# Harvester.net
KiCad netlist of a schematic drawn in Altium Designer
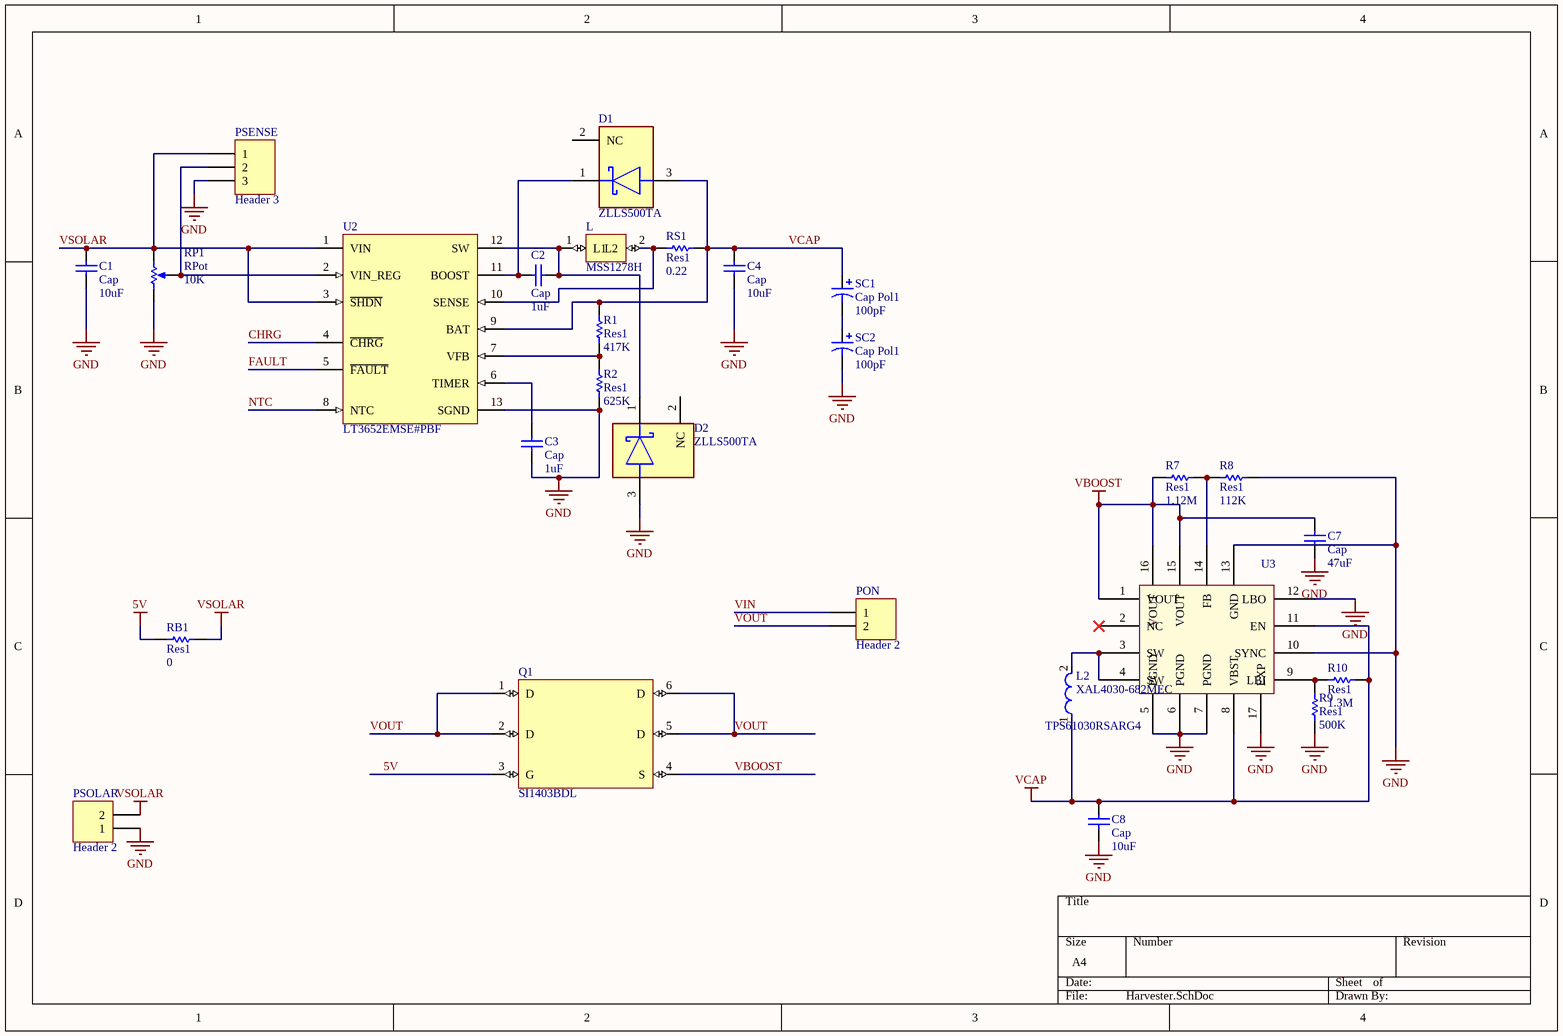
[diagram p0: Harvester.SchDoc]

(export (version "E")
  (design (tool "Eeschema 10.0.6"))
  (components
    (comp (ref "C1")
      (value "Cap")
      (footprint "1812")
      (description "Capacitor")
      (fields (field (name "ALTIUM_VALUE") "10uF") (field (name "PUBLISHER") "Altium Limited"))
      (libsource (lib "Miscellaneous Devices") (part "Cap"))
    )
    (comp (ref "C2")
      (value "Cap")
      (footprint "1812")
      (description "Capacitor")
      (fields (field (name "ALTIUM_VALUE") "1uF") (field (name "PUBLISHER") "Altium Limited"))
      (libsource (lib "Miscellaneous Devices") (part "Cap"))
    )
    (comp (ref "C3")
      (value "Cap")
      (footprint "1812")
      (description "Capacitor")
      (fields (field (name "ALTIUM_VALUE") "1uF") (field (name "PUBLISHER") "Altium Limited"))
      (libsource (lib "Miscellaneous Devices") (part "Cap"))
    )
    (comp (ref "C4")
      (value "Cap")
      (footprint "1812")
      (description "Capacitor")
      (fields (field (name "ALTIUM_VALUE") "10uF") (field (name "PUBLISHER") "Altium Limited"))
      (libsource (lib "Miscellaneous Devices") (part "Cap"))
    )
    (comp (ref "C7")
      (value "Cap")
      (footprint "1812")
      (description "Capacitor")
      (fields (field (name "ALTIUM_VALUE") "47uF") (field (name "PUBLISHER") "Altium Limited"))
      (libsource (lib "Miscellaneous Devices") (part "Cap"))
    )
    (comp (ref "C8")
      (value "Cap")
      (footprint "1608[0603]")
      (description "Capacitor")
      (fields (field (name "ALTIUM_VALUE") "10uF") (field (name "PUBLISHER") "Altium Limited"))
      (libsource (lib "Miscellaneous Devices") (part "Cap"))
    )
    (comp (ref "D1")
      (value "ZLLS500TA")
      (footprint "FP-SOT23-IPC_B")
      (description "DIODE SCHOTTKY 40V 700MA SOT23-3")
      (libsource (lib "") (part "b02bf5cfd78647b0d44792585de17e4_1"))
    )
    (comp (ref "D2")
      (value "ZLLS500TA")
      (footprint "FP-SOT23-IPC_B")
      (description "DIODE SCHOTTKY 40V 700MA SOT23-3")
      (libsource (lib "Altium Content Vault") (part "b02bf5cfd78647b0d44792585de17e4"))
    )
    (comp (ref "L") (value "MSS1278H") (footprint "MSS1278H") (libsource (lib "MSS1278H") (part "MSS1278H")))
    (comp (ref "L2")
      (value "XAL4030-682MEC")
      (footprint "FP-XAL4030-472MEC-MFG")
      (description "Power Inductor (SMD), 6.8 µH, 5.1 A, Shielded, 4.5 A, XAL40xx Series, 4mm x 4mm x 3.1mm")
      (fields (field (name "TOLERANCE") "20%"))
      (libsource (lib "Altium Content Vault") (part "725321dda6339637d4d059423bc1c3c"))
    )
    (comp (ref "PON")
      (value "Header 2")
      (footprint "HDR1X2")
      (description "Header, 2-Pin")
      (fields (field (name "PUBLISHER") "Altium Limited"))
      (libsource (lib "Miscellaneous Connectors") (part "Header 2"))
    )
    (comp (ref "PSENSE")
      (value "Header 3")
      (footprint "HDR1X3")
      (description "Header, 3-Pin")
      (fields (field (name "PUBLISHER") "Altium Limited"))
      (libsource (lib "Miscellaneous Connectors") (part "Header 3"))
    )
    (comp (ref "PSOLAR")
      (value "Header 2")
      (footprint "HDR1X2")
      (description "Header, 2-Pin")
      (fields (field (name "PUBLISHER") "Altium Limited"))
      (libsource (lib "") (part "Header 2_1"))
    )
    (comp (ref "Q1")
      (value "SI1403BDL")
      (footprint "SI1403BDL")
      (description "RC (Pi) EMI Filter 2nd Order Low Pass 2 Channel R = 33Ohms, C = 47pF 6-TSSOP, SC-88, SOT-363")
      (fields (field (name "MP") "USBUF01W6") (field (name "MF") "STMicroelectronics"))
      (libsource (lib "SI1403BDL") (part "SI1403BDL"))
    )
    (comp (ref "R1")
      (value "Res1")
      (footprint "0603R-GENERIC")
      (description "Resistor")
      (fields (field (name "ALTIUM_VALUE") "417K") (field (name "PUBLISHER") "Altium Limited"))
      (libsource (lib "Miscellaneous Devices") (part "Res1"))
    )
    (comp (ref "R2")
      (value "Res1")
      (footprint "0603R-GENERIC")
      (description "Resistor")
      (fields (field (name "ALTIUM_VALUE") "625K") (field (name "PUBLISHER") "Altium Limited"))
      (libsource (lib "Miscellaneous Devices") (part "Res1"))
    )
    (comp (ref "R7")
      (value "Res1")
      (footprint "0603R-GENERIC")
      (description "Resistor")
      (fields (field (name "ALTIUM_VALUE") "1.12M") (field (name "PUBLISHER") "Altium Limited"))
      (libsource (lib "Miscellaneous Devices") (part "Res1"))
    )
    (comp (ref "R8")
      (value "Res1")
      (footprint "0603R-GENERIC")
      (description "Resistor")
      (fields (field (name "ALTIUM_VALUE") "112K") (field (name "PUBLISHER") "Altium Limited"))
      (libsource (lib "Miscellaneous Devices") (part "Res1"))
    )
    (comp (ref "R9")
      (value "Res1")
      (footprint "0603R-GENERIC")
      (description "Resistor")
      (fields (field (name "ALTIUM_VALUE") "500K") (field (name "PUBLISHER") "Altium Limited"))
      (libsource (lib "Miscellaneous Devices") (part "Res1"))
    )
    (comp (ref "R10")
      (value "Res1")
      (footprint "0603R-GENERIC")
      (description "Resistor")
      (fields (field (name "ALTIUM_VALUE") "1.3M") (field (name "PUBLISHER") "Altium Limited"))
      (libsource (lib "Miscellaneous Devices") (part "Res1"))
    )
    (comp (ref "RB1")
      (value "Res1")
      (footprint "0603R-GENERIC")
      (description "Resistor")
      (fields (field (name "ALTIUM_VALUE") "0") (field (name "PUBLISHER") "Altium Limited"))
      (libsource (lib "Miscellaneous Devices") (part "Res1"))
    )
    (comp (ref "RP1")
      (value "RPot")
      (footprint "VR5")
      (description "Potentiometer")
      (fields (field (name "ALTIUM_VALUE") "10K") (field (name "PUBLISHER") "Altium Limited"))
      (libsource (lib "Miscellaneous Devices") (part "RPot"))
    )
    (comp (ref "RS1")
      (value "Res1")
      (footprint "0603R-GENERIC")
      (description "Resistor")
      (fields (field (name "ALTIUM_VALUE") "0.22") (field (name "PUBLISHER") "Altium Limited"))
      (libsource (lib "Miscellaneous Devices") (part "Res1"))
    )
    (comp (ref "SC1")
      (value "Cap Pol1")
      (footprint "RB7.6-15")
      (description "Polarized Capacitor (Radial)")
      (fields (field (name "ALTIUM_VALUE") "100pF") (field (name "PUBLISHER") "Altium Limited"))
      (libsource (lib "Miscellaneous Devices") (part "Cap Pol1"))
    )
    (comp (ref "SC2")
      (value "Cap Pol1")
      (footprint "RB7.6-15")
      (description "Polarized Capacitor (Radial)")
      (fields (field (name "ALTIUM_VALUE") "100pF") (field (name "PUBLISHER") "Altium Limited"))
      (libsource (lib "Miscellaneous Devices") (part "Cap Pol1"))
    )
    (comp (ref "U2")
      (value "LT3652EMSE#PBF")
      (footprint "LT-MSE-12-EDP_M")
      (fields (field (name "MANUFACTURER") "Linear Technology"))
      (libsource (lib "Altium Content Vault") (part "LT-LT3652-MSE-12_3652HV-DD-12"))
    )
    (comp (ref "U3")
      (value "TPS61030RSARG4")
      (footprint "QFN65P400X400X100-17N")
      (libsource (lib "TPS61030RSARG4") (part "TPS61030RSARG4"))
    )
  )
  (nets
    (net (code "1") (name "/CHRG") (class "Default")
      (node (ref "U2") (pin "4") (pinfunction "~{CHRG}_4") (pintype "tri_state"))
    )
    (net (code "2") (name "/FAULT") (class "Default")
      (node (ref "U2") (pin "5") (pinfunction "~{FAULT}_5") (pintype "tri_state"))
    )
    (net (code "3") (name "/NTC") (class "Default")
      (node (ref "U2") (pin "8") (pinfunction "NTC_8") (pintype "input"))
    )
    (net (code "4") (name "/VIN") (class "Default")
      (node (ref "PON") (pin "1") (pinfunction "1_1") (pintype "passive"))
    )
    (net (code "5") (name "/VOUT") (class "Default")
      (node (ref "PON") (pin "2") (pinfunction "2_2") (pintype "passive"))
      (node (ref "Q1") (pin "1") (pinfunction "D_1") (pintype "bidirectional"))
      (node (ref "Q1") (pin "2") (pinfunction "D_2") (pintype "bidirectional"))
      (node (ref "Q1") (pin "5") (pinfunction "D_5") (pintype "bidirectional"))
      (node (ref "Q1") (pin "6") (pinfunction "D_6") (pintype "bidirectional"))
    )
    (net (code "6") (name "5V") (class "Default")
      (node (ref "Q1") (pin "3") (pinfunction "G_3") (pintype "bidirectional"))
      (node (ref "RB1") (pin "1") (pinfunction "1_1") (pintype "passive"))
    )
    (net (code "7") (name "GND") (class "Default")
      (node (ref "C1") (pin "2") (pinfunction "2_2") (pintype "passive"))
      (node (ref "C3") (pin "2") (pinfunction "2_2") (pintype "passive"))
      (node (ref "C4") (pin "2") (pinfunction "2_2") (pintype "passive"))
      (node (ref "C7") (pin "1") (pinfunction "1_1") (pintype "passive"))
      (node (ref "C8") (pin "1") (pinfunction "1_1") (pintype "passive"))
      (node (ref "D2") (pin "3") (pinfunction "A_3") (pintype "passive"))
      (node (ref "PSENSE") (pin "3") (pinfunction "3_3") (pintype "passive"))
      (node (ref "PSOLAR") (pin "1") (pinfunction "1_1") (pintype "passive"))
      (node (ref "R2") (pin "2") (pinfunction "2_2") (pintype "passive"))
      (node (ref "R8") (pin "1") (pinfunction "1_1") (pintype "passive"))
      (node (ref "R9") (pin "2") (pinfunction "2_2") (pintype "passive"))
      (node (ref "RP1") (pin "1") (pinfunction "TOP_1") (pintype "passive"))
      (node (ref "SC2") (pin "2") (pinfunction "2_2") (pintype "passive"))
      (node (ref "U2") (pin "13") (pinfunction "SGND_13") (pintype "power_in"))
      (node (ref "U3") (pin "10") (pinfunction "SYNC_10") (pintype "passive"))
      (node (ref "U3") (pin "12") (pinfunction "LBO_12") (pintype "passive"))
      (node (ref "U3") (pin "13") (pinfunction "GND_13") (pintype "passive"))
      (node (ref "U3") (pin "17") (pinfunction "EXP_17") (pintype "passive"))
      (node (ref "U3") (pin "5") (pinfunction "PGND_5") (pintype "passive"))
      (node (ref "U3") (pin "6") (pinfunction "PGND_6") (pintype "passive"))
      (node (ref "U3") (pin "7") (pinfunction "PGND_7") (pintype "passive"))
    )
    (net (code "8") (name "Net-(D1-C)") (class "Default")
      (node (ref "C2") (pin "1") (pinfunction "1_1") (pintype "passive"))
      (node (ref "D1") (pin "1") (pinfunction "C_1") (pintype "passive"))
      (node (ref "U2") (pin "11") (pinfunction "BOOST_11") (pintype "power_in"))
    )
    (net (code "9") (name "Net-(D2-C)") (class "Default")
      (node (ref "C2") (pin "2") (pinfunction "2_2") (pintype "passive"))
      (node (ref "D2") (pin "1") (pinfunction "C_1") (pintype "passive"))
      (node (ref "L") (pin "1") (pinfunction "L1_1") (pintype "bidirectional"))
      (node (ref "U2") (pin "12") (pinfunction "SW_12") (pintype "power_in"))
    )
    (net (code "10") (name "Net-(L-L2)") (class "Default")
      (node (ref "L") (pin "2") (pinfunction "L2_2") (pintype "bidirectional"))
      (node (ref "RS1") (pin "1") (pinfunction "1_1") (pintype "passive"))
      (node (ref "U2") (pin "10") (pinfunction "SENSE_10") (pintype "input"))
    )
    (net (code "11") (name "Net-(L2-Pad2)") (class "Default")
      (node (ref "L2") (pin "2") (pinfunction "2_2") (pintype "passive"))
      (node (ref "U3") (pin "3") (pinfunction "SW_3") (pintype "passive"))
      (node (ref "U3") (pin "4") (pinfunction "SW_4") (pintype "passive"))
    )
    (net (code "12") (name "Net-(RP1-TAP)") (class "Default")
      (node (ref "PSENSE") (pin "2") (pinfunction "2_2") (pintype "passive"))
      (node (ref "RP1") (pin "3") (pinfunction "TAP_3") (pintype "passive"))
      (node (ref "U2") (pin "2") (pinfunction "VIN_REG_2") (pintype "input"))
    )
    (net (code "13") (name "Net-(SC1-Pad2)") (class "Default")
      (node (ref "SC1") (pin "2") (pinfunction "2_2") (pintype "passive"))
      (node (ref "SC2") (pin "1") (pinfunction "1_1") (pintype "passive"))
    )
    (net (code "14") (name "Net-(U2-TIMER)") (class "Default")
      (node (ref "C3") (pin "1") (pinfunction "1_1") (pintype "passive"))
      (node (ref "U2") (pin "6") (pinfunction "TIMER_6") (pintype "input"))
    )
    (net (code "15") (name "Net-(U2-VFB)") (class "Default")
      (node (ref "R1") (pin "2") (pinfunction "2_2") (pintype "passive"))
      (node (ref "R2") (pin "1") (pinfunction "1_1") (pintype "passive"))
      (node (ref "U2") (pin "7") (pinfunction "VFB_7") (pintype "input"))
    )
    (net (code "16") (name "Net-(U3-FB)") (class "Default")
      (node (ref "R7") (pin "1") (pinfunction "1_1") (pintype "passive"))
      (node (ref "R8") (pin "2") (pinfunction "2_2") (pintype "passive"))
      (node (ref "U3") (pin "14") (pinfunction "FB_14") (pintype "passive"))
    )
    (net (code "17") (name "Net-(U3-LBI)") (class "Default")
      (node (ref "R10") (pin "1") (pinfunction "1_1") (pintype "passive"))
      (node (ref "R9") (pin "1") (pinfunction "1_1") (pintype "passive"))
      (node (ref "U3") (pin "9") (pinfunction "LBI_9") (pintype "passive"))
    )
    (net (code "18") (name "VBOOST") (class "Default")
      (node (ref "C7") (pin "2") (pinfunction "2_2") (pintype "passive"))
      (node (ref "Q1") (pin "4") (pinfunction "S_4") (pintype "bidirectional"))
      (node (ref "R7") (pin "2") (pinfunction "2_2") (pintype "passive"))
      (node (ref "U3") (pin "1") (pinfunction "VOUT_1") (pintype "passive"))
      (node (ref "U3") (pin "15") (pinfunction "VOUT_15") (pintype "passive"))
      (node (ref "U3") (pin "16") (pinfunction "VOUT_16") (pintype "passive"))
    )
    (net (code "19") (name "VCAP") (class "Default")
      (node (ref "C4") (pin "1") (pinfunction "1_1") (pintype "passive"))
      (node (ref "C8") (pin "2") (pinfunction "2_2") (pintype "passive"))
      (node (ref "D1") (pin "3") (pinfunction "A_3") (pintype "passive"))
      (node (ref "L2") (pin "1") (pinfunction "1_1") (pintype "passive"))
      (node (ref "R1") (pin "1") (pinfunction "1_1") (pintype "passive"))
      (node (ref "R10") (pin "2") (pinfunction "2_2") (pintype "passive"))
      (node (ref "RS1") (pin "2") (pinfunction "2_2") (pintype "passive"))
      (node (ref "SC1") (pin "1") (pinfunction "1_1") (pintype "passive"))
      (node (ref "U2") (pin "9") (pinfunction "BAT_9") (pintype "input"))
      (node (ref "U3") (pin "11") (pinfunction "EN_11") (pintype "passive"))
      (node (ref "U3") (pin "8") (pinfunction "VBST_8") (pintype "passive"))
    )
    (net (code "20") (name "VSOLAR") (class "Default")
      (node (ref "C1") (pin "1") (pinfunction "1_1") (pintype "passive"))
      (node (ref "PSENSE") (pin "1") (pinfunction "1_1") (pintype "passive"))
      (node (ref "PSOLAR") (pin "2") (pinfunction "2_2") (pintype "passive"))
      (node (ref "RB1") (pin "2") (pinfunction "2_2") (pintype "passive"))
      (node (ref "RP1") (pin "2") (pinfunction "BOT_2") (pintype "passive"))
      (node (ref "U2") (pin "1") (pinfunction "VIN_1") (pintype "power_in"))
      (node (ref "U2") (pin "3") (pinfunction "~{SHDN}_3") (pintype "input"))
    )
    (net (code "21") (name "unconnected-(D1-NC-Pad2)") (class "Default")
      (node (ref "D1") (pin "2") (pinfunction "NC_2") (pintype "passive"))
    )
    (net (code "22") (name "unconnected-(D2-NC-Pad2)") (class "Default")
      (node (ref "D2") (pin "2") (pinfunction "NC_2") (pintype "passive"))
    )
    (net (code "23") (name "unconnected-(U3-NC-Pad2)") (class "Default")
      (node (ref "U3") (pin "2") (pinfunction "NC_2") (pintype "passive+no_connect"))
    )
  )
)
